# micro.net
KiCad netlist of a schematic drawn in Altium Designer
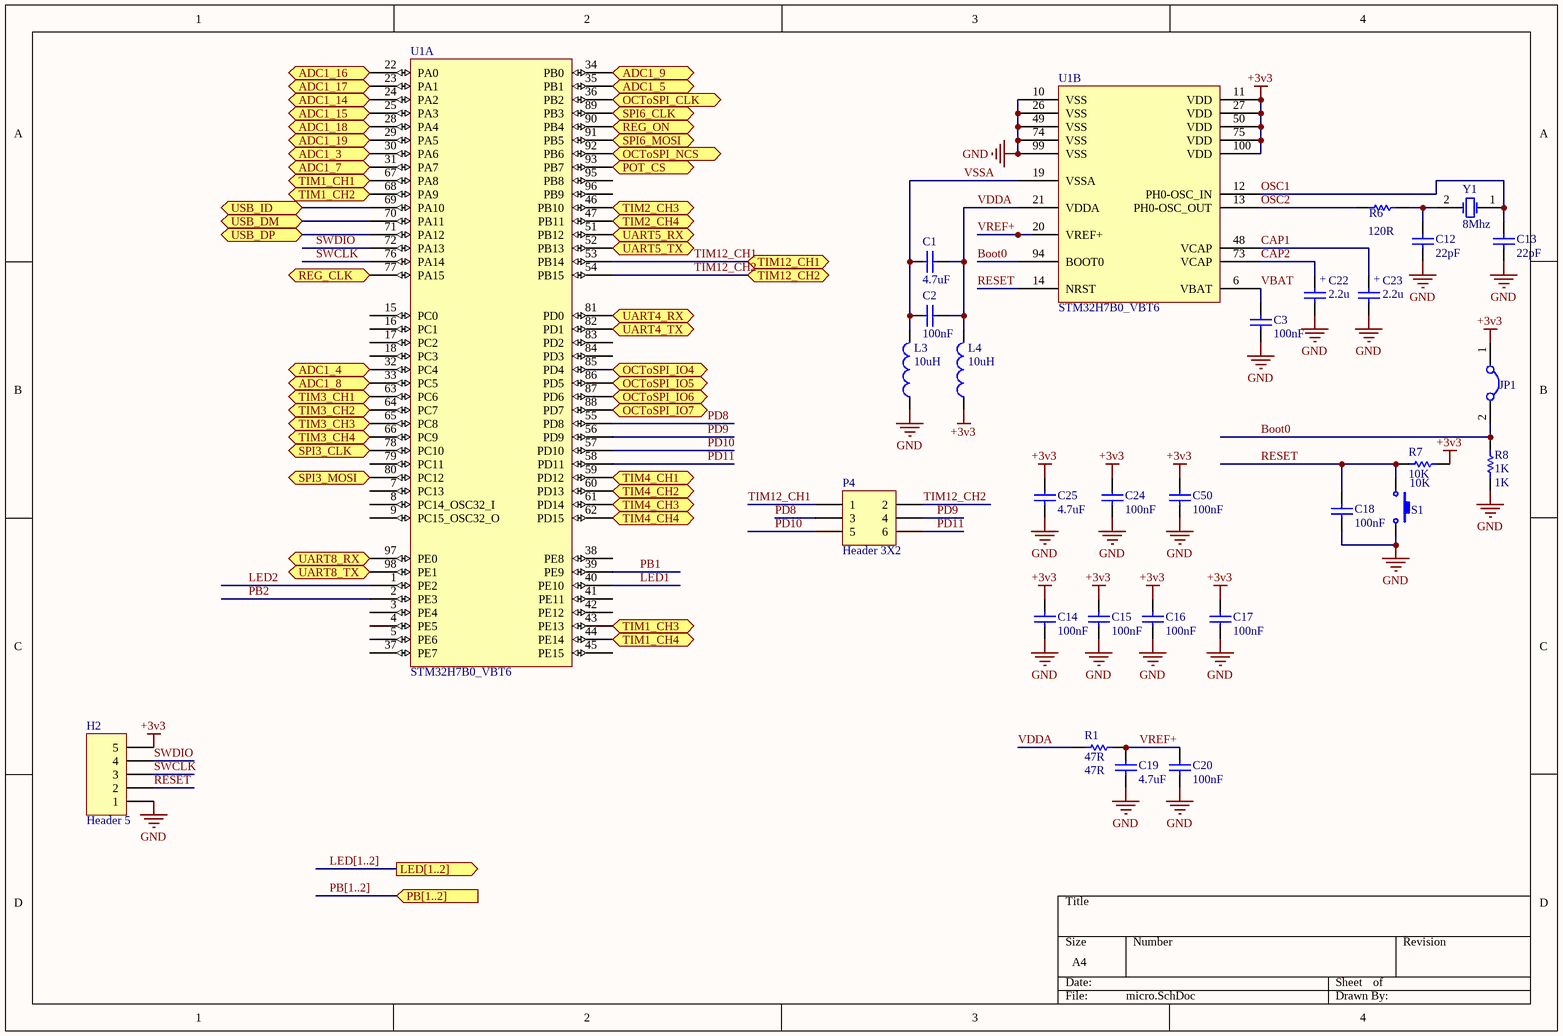
[diagram p0: micro.SchDoc]

(export (version "E")
  (design (tool "Eeschema 10.0.6"))
  (components
    (comp (ref "C1") (value "4.7uF") (footprint "SMD_CAP_0805") (libsource (lib "common0") (part "Cap")))
    (comp (ref "C2") (value "100nF") (footprint "SMD_CAP_0805") (libsource (lib "common0") (part "Cap")))
    (comp (ref "C3") (value "100nF") (footprint "SMD_CAP_0805") (libsource (lib "common0") (part "Cap")))
    (comp (ref "C12")
      (value "22pF")
      (footprint "SMD_CAP_0805")
      (description "Capacitor")
      (fields (field (name "PUBLISHER") "Altium Limited"))
      (libsource (lib "Miscellaneous Devices") (part "Cap"))
    )
    (comp (ref "C13")
      (value "22pF")
      (footprint "SMD_CAP_0805")
      (description "Capacitor")
      (fields (field (name "PUBLISHER") "Altium Limited"))
      (libsource (lib "Miscellaneous Devices") (part "Cap"))
    )
    (comp (ref "C14")
      (value "100nF")
      (footprint "SMD_CAP_0805")
      (description "Capacitor")
      (fields (field (name "PUBLISHER") "Altium Limited"))
      (libsource (lib "Miscellaneous Devices") (part "Cap"))
    )
    (comp (ref "C15")
      (value "100nF")
      (footprint "SMD_CAP_0805")
      (description "Capacitor")
      (fields (field (name "PUBLISHER") "Altium Limited"))
      (libsource (lib "Miscellaneous Devices") (part "Cap"))
    )
    (comp (ref "C16")
      (value "100nF")
      (footprint "SMD_CAP_0805")
      (description "Capacitor")
      (fields (field (name "PUBLISHER") "Altium Limited"))
      (libsource (lib "Miscellaneous Devices") (part "Cap"))
    )
    (comp (ref "C17")
      (value "100nF")
      (footprint "SMD_CAP_0805")
      (description "Capacitor")
      (fields (field (name "PUBLISHER") "Altium Limited"))
      (libsource (lib "Miscellaneous Devices") (part "Cap"))
    )
    (comp (ref "C18")
      (value "100nF")
      (footprint "SMD_CAP_0805")
      (description "Capacitor")
      (fields (field (name "PUBLISHER") "Altium Limited"))
      (libsource (lib "Miscellaneous Devices") (part "Cap"))
    )
    (comp (ref "C19") (value "4.7uF") (footprint "SMD_CAP_0805") (libsource (lib "common0") (part "Cap")))
    (comp (ref "C20")
      (value "100nF")
      (footprint "SMD_CAP_0805")
      (description "Capacitor")
      (fields (field (name "PUBLISHER") "Altium Limited"))
      (libsource (lib "Miscellaneous Devices") (part "Cap"))
    )
    (comp (ref "C22")
      (value "2.2u")
      (footprint "SMD_CAP_0805")
      (description "tantal size a")
      (libsource (lib "Altium library (www.AVRelec.com)") (part "Cap Pol"))
    )
    (comp (ref "C23")
      (value "2.2u")
      (footprint "SMD_CAP_0805")
      (description "tantal size a")
      (libsource (lib "Altium library (www.AVRelec.com)") (part "Cap Pol"))
    )
    (comp (ref "C24")
      (value "100nF")
      (footprint "SMD_CAP_0805")
      (description "Capacitor")
      (fields (field (name "PUBLISHER") "Altium Limited"))
      (libsource (lib "Miscellaneous Devices") (part "Cap"))
    )
    (comp (ref "C25") (value "4.7uF") (footprint "SMD_CAP_0805") (libsource (lib "common0") (part "Cap")))
    (comp (ref "C50") (value "100nF") (footprint "SMD_CAP_0805") (libsource (lib "common0") (part "Cap")))
    (comp (ref "H2")
      (value "Header 5")
      (footprint "HDR1X5")
      (description "Header, 5-Pin")
      (fields (field (name "PUBLISHER") "Altium Limited"))
      (libsource (lib "Miscellaneous Connectors") (part "Header 5"))
    )
    (comp (ref "JP1")
      (value "Jumper")
      (footprint "Jumper Small - 2.54 - GRAY")
      (libsource (lib "Altium (2)") (part "Jumper"))
    )
    (comp (ref "L3")
      (value "10uH")
      (footprint "IND1206")
      (description "Inductor")
      (fields (field (name "Comment") "inductor 10uH") (field (name "PUBLISHER") "Altium Limited"))
      (libsource (lib "Miscellaneous Devices") (part "Inductor"))
    )
    (comp (ref "L4")
      (value "10uH")
      (footprint "IND1206")
      (description "Inductor")
      (fields (field (name "Comment") "inductor 10uH") (field (name "PUBLISHER") "Altium Limited"))
      (libsource (lib "Miscellaneous Devices") (part "Inductor"))
    )
    (comp (ref "P4")
      (value "Header 3X2")
      (footprint "HDR2X3")
      (description "Header, 3-Pin, Dual row")
      (fields (field (name "PUBLISHER") "Altium Limited"))
      (libsource (lib "Miscellaneous Connectors") (part "Header 3X2"))
    )
    (comp (ref "R1")
      (value "47R")
      (footprint "RES 0805 (2012X06L)")
      (description "Resistor")
      (fields (field (name "ALTIUM_VALUE") "47R") (field (name "PUBLISHER") "Altium Limited"))
      (libsource (lib "Miscellaneous Devices") (part "Res1"))
    )
    (comp (ref "R6")
      (value "120R")
      (footprint "RES 0805 (2012X06L)")
      (description "Resistor")
      (fields (field (name "PUBLISHER") "Altium Limited"))
      (libsource (lib "Miscellaneous Devices") (part "Res1"))
    )
    (comp (ref "R7")
      (value "10K")
      (footprint "RES 0805 (2012X06L)")
      (description "Resistor")
      (fields (field (name "ALTIUM_VALUE") "10K") (field (name "PUBLISHER") "Altium Limited"))
      (libsource (lib "Miscellaneous Devices") (part "Res1"))
    )
    (comp (ref "R8")
      (value "1K")
      (footprint "RES 0805 (2012X06L)")
      (description "Resistor")
      (fields (field (name "ALTIUM_VALUE") "1K") (field (name "PUBLISHER") "Altium Limited"))
      (libsource (lib "Miscellaneous Devices") (part "Res1"))
    )
    (comp (ref "S1")
      (value "Switch PB")
      (footprint "Switch - Push to On")
      (description "Push Button Switch")
      (libsource (lib "Altium (2)") (part "Switch PB"))
    )
    (comp (ref "U1")
      (value "STM32H7B0_VBT6")
      (footprint "ST Microcontroller 32-Bit STM32:LQFP100_N")
      (description "STM32H7B0_VBT6 LQPF100")
      (libsource (lib "stm32H7b0") (part "STM32H7B0_VBT6"))
    )
    (comp (ref "Y1")
      (value "8Mhz")
      (footprint "CRYSTAL Small")
      (description "Crystal Oscillator")
      (fields (field (name "PUBLISHER") "Altium Limited"))
      (libsource (lib "Miscellaneous Devices") (part "XTAL"))
    )
  )
  (nets
    (net (code "1") (name "+3v3") (class "Default")
      (node (ref "C14") (pin "2") (pinfunction "2_2") (pintype "passive"))
      (node (ref "C15") (pin "2") (pinfunction "2_2") (pintype "passive"))
      (node (ref "C16") (pin "2") (pinfunction "2_2") (pintype "passive"))
      (node (ref "C17") (pin "2") (pinfunction "2_2") (pintype "passive"))
      (node (ref "C24") (pin "2") (pinfunction "2_2") (pintype "passive"))
      (node (ref "C25") (pin "1") (pinfunction "1_1") (pintype "passive"))
      (node (ref "C50") (pin "1") (pinfunction "1_1") (pintype "passive"))
      (node (ref "H2") (pin "5") (pinfunction "5_5") (pintype "passive"))
      (node (ref "JP1") (pin "1") (pinfunction "1_1") (pintype "passive"))
      (node (ref "L4") (pin "1") (pinfunction "1_1") (pintype "passive"))
      (node (ref "R7") (pin "1") (pinfunction "1_1") (pintype "passive"))
      (node (ref "U1") (pin "100") (pinfunction "VDD_100") (pintype "power_in"))
      (node (ref "U1") (pin "11") (pinfunction "VDD_11") (pintype "power_in"))
      (node (ref "U1") (pin "27") (pinfunction "VDD_27") (pintype "power_in"))
      (node (ref "U1") (pin "50") (pinfunction "VDD_50") (pintype "power_in"))
      (node (ref "U1") (pin "75") (pinfunction "VDD_75") (pintype "power_in"))
    )
    (net (code "2") (name "/ADC1_3") (class "Default")
      (node (ref "U1") (pin "30") (pinfunction "PA6_30") (pintype "bidirectional"))
    )
    (net (code "3") (name "/ADC1_4") (class "Default")
      (node (ref "U1") (pin "32") (pinfunction "PC4_32") (pintype "bidirectional"))
    )
    (net (code "4") (name "/ADC1_5") (class "Default")
      (node (ref "U1") (pin "35") (pinfunction "PB1_35") (pintype "bidirectional"))
    )
    (net (code "5") (name "/ADC1_7") (class "Default")
      (node (ref "U1") (pin "31") (pinfunction "PA7_31") (pintype "bidirectional"))
    )
    (net (code "6") (name "/ADC1_8") (class "Default")
      (node (ref "U1") (pin "33") (pinfunction "PC5_33") (pintype "bidirectional"))
    )
    (net (code "7") (name "/ADC1_9") (class "Default")
      (node (ref "U1") (pin "34") (pinfunction "PB0_34") (pintype "bidirectional"))
    )
    (net (code "8") (name "/ADC1_14") (class "Default")
      (node (ref "U1") (pin "24") (pinfunction "PA2_24") (pintype "bidirectional"))
    )
    (net (code "9") (name "/ADC1_15") (class "Default")
      (node (ref "U1") (pin "25") (pinfunction "PA3_25") (pintype "bidirectional"))
    )
    (net (code "10") (name "/ADC1_16") (class "Default")
      (node (ref "U1") (pin "22") (pinfunction "PA0_22") (pintype "bidirectional"))
    )
    (net (code "11") (name "/ADC1_17") (class "Default")
      (node (ref "U1") (pin "23") (pinfunction "PA1_23") (pintype "bidirectional"))
    )
    (net (code "12") (name "/ADC1_18") (class "Default")
      (node (ref "U1") (pin "28") (pinfunction "PA4_28") (pintype "bidirectional"))
    )
    (net (code "13") (name "/ADC1_19") (class "Default")
      (node (ref "U1") (pin "29") (pinfunction "PA5_29") (pintype "bidirectional"))
    )
    (net (code "14") (name "/Boot0") (class "Default")
      (node (ref "JP1") (pin "2") (pinfunction "2_2") (pintype "passive"))
      (node (ref "R8") (pin "2") (pinfunction "2_2") (pintype "passive"))
      (node (ref "U1") (pin "94") (pinfunction "BOOT0_94") (pintype "power_in"))
    )
    (net (code "15") (name "/CAP1") (class "Default")
      (node (ref "C23") (pin "+") (pinfunction "+_+") (pintype "passive"))
      (node (ref "U1") (pin "48") (pinfunction "VCAP_48") (pintype "power_in"))
    )
    (net (code "16") (name "/CAP2") (class "Default")
      (node (ref "C22") (pin "+") (pinfunction "+_+") (pintype "passive"))
      (node (ref "U1") (pin "73") (pinfunction "VCAP_73") (pintype "power_in"))
    )
    (net (code "17") (name "/LED1") (class "Default")
      (node (ref "U1") (pin "40") (pinfunction "PE10_40") (pintype "bidirectional"))
    )
    (net (code "18") (name "/LED2") (class "Default")
      (node (ref "U1") (pin "1") (pinfunction "PE2_1") (pintype "bidirectional"))
    )
    (net (code "20") (name "/OCToSPI_CLK") (class "Default")
      (node (ref "U1") (pin "36") (pinfunction "PB2_36") (pintype "bidirectional"))
    )
    (net (code "21") (name "/OCToSPI_IO4") (class "Default")
      (node (ref "U1") (pin "85") (pinfunction "PD4_85") (pintype "bidirectional"))
    )
    (net (code "22") (name "/OCToSPI_IO5") (class "Default")
      (node (ref "U1") (pin "86") (pinfunction "PD5_86") (pintype "bidirectional"))
    )
    (net (code "23") (name "/OCToSPI_IO6") (class "Default")
      (node (ref "U1") (pin "87") (pinfunction "PD6_87") (pintype "bidirectional"))
    )
    (net (code "24") (name "/OCToSPI_IO7") (class "Default")
      (node (ref "U1") (pin "88") (pinfunction "PD7_88") (pintype "bidirectional"))
    )
    (net (code "25") (name "/OCToSPI_NCS") (class "Default")
      (node (ref "U1") (pin "92") (pinfunction "PB6_92") (pintype "bidirectional"))
    )
    (net (code "26") (name "/OSC1") (class "Default")
      (node (ref "C13") (pin "2") (pinfunction "2_2") (pintype "passive"))
      (node (ref "U1") (pin "12") (pinfunction "PH0-OSC_IN_12") (pintype "power_in"))
      (node (ref "Y1") (pin "1") (pinfunction "OSC1_1") (pintype "passive"))
    )
    (net (code "27") (name "/OSC2") (class "Default")
      (node (ref "R6") (pin "1") (pinfunction "1_1") (pintype "passive"))
      (node (ref "U1") (pin "13") (pinfunction "PH0-OSC_OUT_13") (pintype "power_in"))
    )
    (net (code "28") (name "/PB1") (class "Default")
      (node (ref "U1") (pin "39") (pinfunction "PE9_39") (pintype "bidirectional"))
    )
    (net (code "29") (name "/PB2") (class "Default")
      (node (ref "U1") (pin "2") (pinfunction "PE3_2") (pintype "bidirectional"))
    )
    (net (code "31") (name "/PD8") (class "Default")
      (node (ref "P4") (pin "3") (pinfunction "3_3") (pintype "passive"))
      (node (ref "U1") (pin "55") (pinfunction "PD8_55") (pintype "bidirectional"))
    )
    (net (code "32") (name "/PD9") (class "Default")
      (node (ref "P4") (pin "4") (pinfunction "4_4") (pintype "passive"))
      (node (ref "U1") (pin "56") (pinfunction "PD9_56") (pintype "bidirectional"))
    )
    (net (code "33") (name "/PD10") (class "Default")
      (node (ref "P4") (pin "5") (pinfunction "5_5") (pintype "passive"))
      (node (ref "U1") (pin "57") (pinfunction "PD10_57") (pintype "bidirectional"))
    )
    (net (code "34") (name "/PD11") (class "Default")
      (node (ref "P4") (pin "6") (pinfunction "6_6") (pintype "passive"))
      (node (ref "U1") (pin "58") (pinfunction "PD11_58") (pintype "bidirectional"))
    )
    (net (code "35") (name "/POT_CS") (class "Default")
      (node (ref "U1") (pin "93") (pinfunction "PB7_93") (pintype "bidirectional"))
    )
    (net (code "36") (name "/REG_CLK") (class "Default")
      (node (ref "U1") (pin "77") (pinfunction "PA15_77") (pintype "bidirectional"))
    )
    (net (code "37") (name "/REG_ON") (class "Default")
      (node (ref "U1") (pin "90") (pinfunction "PB4_90") (pintype "bidirectional"))
    )
    (net (code "38") (name "/RESET") (class "Default")
      (node (ref "C18") (pin "2") (pinfunction "2_2") (pintype "passive"))
      (node (ref "H2") (pin "2") (pinfunction "2_2") (pintype "passive"))
      (node (ref "R7") (pin "2") (pinfunction "2_2") (pintype "passive"))
      (node (ref "S1") (pin "1") (pinfunction "1_1") (pintype "passive"))
      (node (ref "U1") (pin "14") (pinfunction "NRST_14") (pintype "power_in"))
    )
    (net (code "39") (name "/SPI3_CLK") (class "Default")
      (node (ref "U1") (pin "78") (pinfunction "PC10_78") (pintype "bidirectional"))
    )
    (net (code "40") (name "/SPI3_MOSI") (class "Default")
      (node (ref "U1") (pin "80") (pinfunction "PC12_80") (pintype "bidirectional"))
    )
    (net (code "41") (name "/SPI6_CLK") (class "Default")
      (node (ref "U1") (pin "89") (pinfunction "PB3_89") (pintype "bidirectional"))
    )
    (net (code "42") (name "/SPI6_MOSI") (class "Default")
      (node (ref "U1") (pin "91") (pinfunction "PB5_91") (pintype "bidirectional"))
    )
    (net (code "43") (name "/SWCLK") (class "Default")
      (node (ref "H2") (pin "3") (pinfunction "3_3") (pintype "passive"))
      (node (ref "U1") (pin "76") (pinfunction "PA14_76") (pintype "bidirectional"))
    )
    (net (code "44") (name "/SWDIO") (class "Default")
      (node (ref "H2") (pin "4") (pinfunction "4_4") (pintype "passive"))
      (node (ref "U1") (pin "72") (pinfunction "PA13_72") (pintype "bidirectional"))
    )
    (net (code "45") (name "/TIM1_CH1") (class "Default")
      (node (ref "U1") (pin "67") (pinfunction "PA8_67") (pintype "bidirectional"))
    )
    (net (code "46") (name "/TIM1_CH2") (class "Default")
      (node (ref "U1") (pin "68") (pinfunction "PA9_68") (pintype "bidirectional"))
    )
    (net (code "47") (name "/TIM1_CH3") (class "Default")
      (node (ref "U1") (pin "43") (pinfunction "PE13_43") (pintype "bidirectional"))
    )
    (net (code "48") (name "/TIM1_CH4") (class "Default")
      (node (ref "U1") (pin "44") (pinfunction "PE14_44") (pintype "bidirectional"))
    )
    (net (code "49") (name "/TIM2_CH3") (class "Default")
      (node (ref "U1") (pin "46") (pinfunction "PB10_46") (pintype "bidirectional"))
    )
    (net (code "50") (name "/TIM2_CH4") (class "Default")
      (node (ref "U1") (pin "47") (pinfunction "PB11_47") (pintype "bidirectional"))
    )
    (net (code "51") (name "/TIM3_CH1") (class "Default")
      (node (ref "U1") (pin "63") (pinfunction "PC6_63") (pintype "bidirectional"))
    )
    (net (code "52") (name "/TIM3_CH2") (class "Default")
      (node (ref "U1") (pin "64") (pinfunction "PC7_64") (pintype "bidirectional"))
    )
    (net (code "53") (name "/TIM3_CH3") (class "Default")
      (node (ref "U1") (pin "65") (pinfunction "PC8_65") (pintype "bidirectional"))
    )
    (net (code "54") (name "/TIM3_CH4") (class "Default")
      (node (ref "U1") (pin "66") (pinfunction "PC9_66") (pintype "bidirectional"))
    )
    (net (code "55") (name "/TIM4_CH1") (class "Default")
      (node (ref "U1") (pin "59") (pinfunction "PD12_59") (pintype "bidirectional"))
    )
    (net (code "56") (name "/TIM4_CH2") (class "Default")
      (node (ref "U1") (pin "60") (pinfunction "PD13_60") (pintype "bidirectional"))
    )
    (net (code "57") (name "/TIM4_CH3") (class "Default")
      (node (ref "U1") (pin "61") (pinfunction "PD14_61") (pintype "bidirectional"))
    )
    (net (code "58") (name "/TIM4_CH4") (class "Default")
      (node (ref "U1") (pin "62") (pinfunction "PD15_62") (pintype "bidirectional"))
    )
    (net (code "59") (name "/TIM12_CH1") (class "Default")
      (node (ref "P4") (pin "1") (pinfunction "1_1") (pintype "passive"))
      (node (ref "U1") (pin "53") (pinfunction "PB14_53") (pintype "bidirectional"))
    )
    (net (code "60") (name "/TIM12_CH2") (class "Default")
      (node (ref "P4") (pin "2") (pinfunction "2_2") (pintype "passive"))
      (node (ref "U1") (pin "54") (pinfunction "PB15_54") (pintype "bidirectional"))
    )
    (net (code "61") (name "/UART4_RX") (class "Default")
      (node (ref "U1") (pin "81") (pinfunction "PD0_81") (pintype "bidirectional"))
    )
    (net (code "62") (name "/UART4_TX") (class "Default")
      (node (ref "U1") (pin "82") (pinfunction "PD1_82") (pintype "bidirectional"))
    )
    (net (code "63") (name "/UART5_RX") (class "Default")
      (node (ref "U1") (pin "51") (pinfunction "PB12_51") (pintype "bidirectional"))
    )
    (net (code "64") (name "/UART5_TX") (class "Default")
      (node (ref "U1") (pin "52") (pinfunction "PB13_52") (pintype "bidirectional"))
    )
    (net (code "65") (name "/UART8_RX") (class "Default")
      (node (ref "U1") (pin "97") (pinfunction "PE0_97") (pintype "bidirectional"))
    )
    (net (code "66") (name "/UART8_TX") (class "Default")
      (node (ref "U1") (pin "98") (pinfunction "PE1_98") (pintype "bidirectional"))
    )
    (net (code "67") (name "/USB_DM") (class "Default")
      (node (ref "U1") (pin "70") (pinfunction "PA11_70") (pintype "bidirectional"))
    )
    (net (code "68") (name "/USB_DP") (class "Default")
      (node (ref "U1") (pin "71") (pinfunction "PA12_71") (pintype "bidirectional"))
    )
    (net (code "69") (name "/USB_ID") (class "Default")
      (node (ref "U1") (pin "69") (pinfunction "PA10_69") (pintype "bidirectional"))
    )
    (net (code "70") (name "/VBAT") (class "Default")
      (node (ref "C3") (pin "2") (pinfunction "2_2") (pintype "passive"))
      (node (ref "U1") (pin "6") (pinfunction "VBAT_6") (pintype "power_in"))
    )
    (net (code "71") (name "/VDDA") (class "Default")
      (node (ref "C1") (pin "2") (pinfunction "2_2") (pintype "passive"))
      (node (ref "C2") (pin "2") (pinfunction "2_2") (pintype "passive"))
      (node (ref "L4") (pin "2") (pinfunction "2_2") (pintype "passive"))
      (node (ref "R1") (pin "2") (pinfunction "2_2") (pintype "passive"))
      (node (ref "U1") (pin "21") (pinfunction "VDDA_21") (pintype "power_in"))
    )
    (net (code "72") (name "/VREF+") (class "Default")
      (node (ref "C19") (pin "1") (pinfunction "1_1") (pintype "passive"))
      (node (ref "C20") (pin "2") (pinfunction "2_2") (pintype "passive"))
      (node (ref "R1") (pin "1") (pinfunction "1_1") (pintype "passive"))
      (node (ref "U1") (pin "20") (pinfunction "VREF+_20") (pintype "power_in"))
    )
    (net (code "73") (name "/VSSA") (class "Default")
      (node (ref "C1") (pin "1") (pinfunction "1_1") (pintype "passive"))
      (node (ref "C2") (pin "1") (pinfunction "1_1") (pintype "passive"))
      (node (ref "L3") (pin "2") (pinfunction "2_2") (pintype "passive"))
      (node (ref "U1") (pin "19") (pinfunction "VSSA_19") (pintype "power_in"))
    )
    (net (code "74") (name "GND") (class "Default")
      (node (ref "C12") (pin "1") (pinfunction "1_1") (pintype "passive"))
      (node (ref "C13") (pin "1") (pinfunction "1_1") (pintype "passive"))
      (node (ref "C14") (pin "1") (pinfunction "1_1") (pintype "passive"))
      (node (ref "C15") (pin "1") (pinfunction "1_1") (pintype "passive"))
      (node (ref "C16") (pin "1") (pinfunction "1_1") (pintype "passive"))
      (node (ref "C17") (pin "1") (pinfunction "1_1") (pintype "passive"))
      (node (ref "C18") (pin "1") (pinfunction "1_1") (pintype "passive"))
      (node (ref "C19") (pin "2") (pinfunction "2_2") (pintype "passive"))
      (node (ref "C20") (pin "1") (pinfunction "1_1") (pintype "passive"))
      (node (ref "C22") (pin "-") (pinfunction "-_-") (pintype "passive"))
      (node (ref "C23") (pin "-") (pinfunction "-_-") (pintype "passive"))
      (node (ref "C24") (pin "1") (pinfunction "1_1") (pintype "passive"))
      (node (ref "C25") (pin "2") (pinfunction "2_2") (pintype "passive"))
      (node (ref "C3") (pin "1") (pinfunction "1_1") (pintype "passive"))
      (node (ref "C50") (pin "2") (pinfunction "2_2") (pintype "passive"))
      (node (ref "H2") (pin "1") (pinfunction "1_1") (pintype "passive"))
      (node (ref "L3") (pin "1") (pinfunction "1_1") (pintype "passive"))
      (node (ref "R8") (pin "1") (pinfunction "1_1") (pintype "passive"))
      (node (ref "S1") (pin "2") (pinfunction "2_2") (pintype "passive"))
      (node (ref "U1") (pin "10") (pinfunction "VSS_10") (pintype "power_in"))
      (node (ref "U1") (pin "26") (pinfunction "VSS_26") (pintype "power_in"))
      (node (ref "U1") (pin "49") (pinfunction "VSS_49") (pintype "power_in"))
      (node (ref "U1") (pin "74") (pinfunction "VSS_74") (pintype "power_in"))
      (node (ref "U1") (pin "99") (pinfunction "VSS_99") (pintype "power_in"))
    )
    (net (code "75") (name "Net-(Y1-OSC2)") (class "Default")
      (node (ref "C12") (pin "2") (pinfunction "2_2") (pintype "passive"))
      (node (ref "R6") (pin "2") (pinfunction "2_2") (pintype "passive"))
      (node (ref "Y1") (pin "2") (pinfunction "OSC2_2") (pintype "passive"))
    )
    (net (code "76") (name "unconnected-(U1A-PB8-Pad95)") (class "Default")
      (node (ref "U1") (pin "95") (pinfunction "PB8_95") (pintype "bidirectional"))
    )
    (net (code "77") (name "unconnected-(U1A-PB9-Pad96)") (class "Default")
      (node (ref "U1") (pin "96") (pinfunction "PB9_96") (pintype "bidirectional"))
    )
    (net (code "78") (name "unconnected-(U1A-PC0-Pad15)") (class "Default")
      (node (ref "U1") (pin "15") (pinfunction "PC0_15") (pintype "bidirectional"))
    )
    (net (code "79") (name "unconnected-(U1A-PC1-Pad16)") (class "Default")
      (node (ref "U1") (pin "16") (pinfunction "PC1_16") (pintype "bidirectional"))
    )
    (net (code "80") (name "unconnected-(U1A-PC2-Pad17)") (class "Default")
      (node (ref "U1") (pin "17") (pinfunction "PC2_17") (pintype "bidirectional"))
    )
    (net (code "81") (name "unconnected-(U1A-PC3-Pad18)") (class "Default")
      (node (ref "U1") (pin "18") (pinfunction "PC3_18") (pintype "bidirectional"))
    )
    (net (code "82") (name "unconnected-(U1A-PC11-Pad79)") (class "Default")
      (node (ref "U1") (pin "79") (pinfunction "PC11_79") (pintype "bidirectional"))
    )
    (net (code "83") (name "unconnected-(U1A-PC13-Pad7)") (class "Default")
      (node (ref "U1") (pin "7") (pinfunction "PC13_7") (pintype "bidirectional"))
    )
    (net (code "84") (name "unconnected-(U1A-PC14_OSC32_I-Pad8)") (class "Default")
      (node (ref "U1") (pin "8") (pinfunction "PC14_OSC32_I_8") (pintype "bidirectional"))
    )
    (net (code "85") (name "unconnected-(U1A-PC15_OSC32_O-Pad9)") (class "Default")
      (node (ref "U1") (pin "9") (pinfunction "PC15_OSC32_O_9") (pintype "bidirectional"))
    )
    (net (code "86") (name "unconnected-(U1A-PD2-Pad83)") (class "Default")
      (node (ref "U1") (pin "83") (pinfunction "PD2_83") (pintype "bidirectional"))
    )
    (net (code "87") (name "unconnected-(U1A-PD3-Pad84)") (class "Default")
      (node (ref "U1") (pin "84") (pinfunction "PD3_84") (pintype "bidirectional"))
    )
    (net (code "88") (name "unconnected-(U1A-PE4-Pad3)") (class "Default")
      (node (ref "U1") (pin "3") (pinfunction "PE4_3") (pintype "bidirectional"))
    )
    (net (code "89") (name "unconnected-(U1A-PE5-Pad4)") (class "Default")
      (node (ref "U1") (pin "4") (pinfunction "PE5_4") (pintype "bidirectional"))
    )
    (net (code "90") (name "unconnected-(U1A-PE6-Pad5)") (class "Default")
      (node (ref "U1") (pin "5") (pinfunction "PE6_5") (pintype "bidirectional"))
    )
    (net (code "91") (name "unconnected-(U1A-PE7-Pad37)") (class "Default")
      (node (ref "U1") (pin "37") (pinfunction "PE7_37") (pintype "bidirectional"))
    )
    (net (code "92") (name "unconnected-(U1A-PE8-Pad38)") (class "Default")
      (node (ref "U1") (pin "38") (pinfunction "PE8_38") (pintype "bidirectional"))
    )
    (net (code "93") (name "unconnected-(U1A-PE11-Pad41)") (class "Default")
      (node (ref "U1") (pin "41") (pinfunction "PE11_41") (pintype "bidirectional"))
    )
    (net (code "94") (name "unconnected-(U1A-PE12-Pad42)") (class "Default")
      (node (ref "U1") (pin "42") (pinfunction "PE12_42") (pintype "bidirectional"))
    )
    (net (code "95") (name "unconnected-(U1A-PE15-Pad45)") (class "Default")
      (node (ref "U1") (pin "45") (pinfunction "PE15_45") (pintype "bidirectional"))
    )
  )
)
